# OUTPUTS.net
KiCad netlist of a schematic drawn in Altium Designer
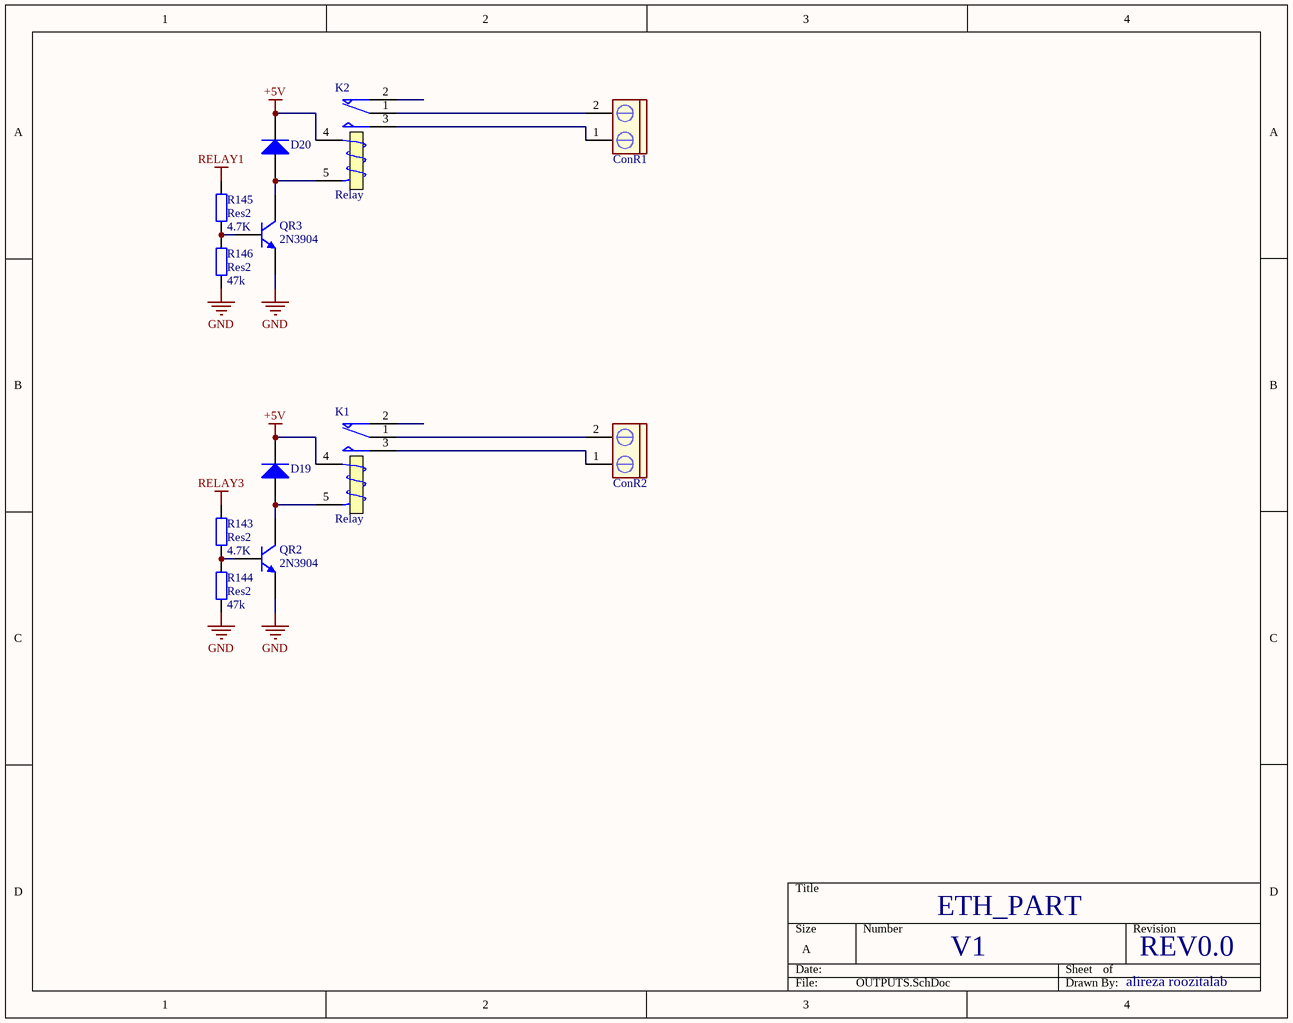
[diagram p0: OUTPUTS.SchDoc]

(export (version "E")
  (design (tool "Eeschema 10.0.6"))
  (components
    (comp (ref "ConR1")
      (value "CON2 pin blue")
      (footprint "My_CN2")
      (description "Connector blue screw")
      (libsource (lib "Mylib") (part "CON2 pin blue"))
    )
    (comp (ref "ConR2")
      (value "CON2 pin blue")
      (footprint "My_CN2")
      (description "Connector blue screw")
      (libsource (lib "Mylib") (part "CON2 pin blue"))
    )
    (comp (ref "D19")
      (value "Diode 1N4148")
      (footprint "Diode-1n4148 - SMD PAD")
      (description "High Conductance Fast Diode")
      (fields (field (name "PUBLISHER") "Altium Limited"))
      (libsource (lib "Miscellaneous Devices") (part "Diode 1N4148"))
    )
    (comp (ref "D20")
      (value "Diode 1N4148")
      (footprint "Diode-1n4148 - SMD PAD")
      (description "High Conductance Fast Diode")
      (fields (field (name "PUBLISHER") "Altium Limited"))
      (libsource (lib "Miscellaneous Devices") (part "Diode 1N4148"))
    )
    (comp (ref "K1")
      (value "Relay")
      (footprint "Relay 18.85x15.35x15.70")
      (description "SPDT Relay")
      (fields (field (name "PUBLISHER") "Altium Limited"))
      (libsource (lib "Miscellaneous Devices") (part "Relay"))
    )
    (comp (ref "K2")
      (value "Relay")
      (footprint "Relay 18.85x15.35x15.70")
      (description "SPDT Relay")
      (fields (field (name "PUBLISHER") "Altium Limited"))
      (libsource (lib "Miscellaneous Devices") (part "Relay"))
    )
    (comp (ref "QR2")
      (value "2N3904")
      (footprint "2N3906_SMD")
      (description "NPN General Purpose Amplifier")
      (fields (field (name "PUBLISHER") "Altium Limited"))
      (libsource (lib "Miscellaneous Devices") (part "2N3904"))
    )
    (comp (ref "QR3")
      (value "2N3904")
      (footprint "2N3906_SMD")
      (description "NPN General Purpose Amplifier")
      (fields (field (name "PUBLISHER") "Altium Limited"))
      (libsource (lib "Miscellaneous Devices") (part "2N3904"))
    )
    (comp (ref "R143")
      (value "Res2")
      (footprint "RES 1206 (3216X08L)")
      (description "Resistor")
      (fields (field (name "ALTIUM_VALUE") "4.7K") (field (name "PUBLISHER") "Altium Limited"))
      (libsource (lib "Miscellaneous Devices") (part "Res2"))
    )
    (comp (ref "R144")
      (value "Res2")
      (footprint "RES 1206 (3216X08L)")
      (description "Resistor")
      (fields (field (name "ALTIUM_VALUE") "47k") (field (name "PUBLISHER") "Altium Limited"))
      (libsource (lib "Miscellaneous Devices") (part "Res2"))
    )
    (comp (ref "R145")
      (value "Res2")
      (footprint "RES 1206 (3216X08L)")
      (description "Resistor")
      (fields (field (name "ALTIUM_VALUE") "4.7K") (field (name "PUBLISHER") "Altium Limited"))
      (libsource (lib "Miscellaneous Devices") (part "Res2"))
    )
    (comp (ref "R146")
      (value "Res2")
      (footprint "RES 1206 (3216X08L)")
      (description "Resistor")
      (fields (field (name "ALTIUM_VALUE") "47k") (field (name "PUBLISHER") "Altium Limited"))
      (libsource (lib "Miscellaneous Devices") (part "Res2"))
    )
  )
  (nets
    (net (code "1") (name "+5V") (class "Default")
      (node (ref "D19") (pin "2") (pinfunction "K_2") (pintype "passive"))
      (node (ref "D20") (pin "2") (pinfunction "K_2") (pintype "passive"))
      (node (ref "K1") (pin "4") (pinfunction "T1_4") (pintype "passive"))
      (node (ref "K2") (pin "4") (pinfunction "T1_4") (pintype "passive"))
    )
    (net (code "2") (name "GND") (class "Default")
      (node (ref "QR2") (pin "1") (pinfunction "E_1") (pintype "passive"))
      (node (ref "QR3") (pin "1") (pinfunction "E_1") (pintype "passive"))
      (node (ref "R144") (pin "1") (pinfunction "1_1") (pintype "passive"))
      (node (ref "R146") (pin "1") (pinfunction "1_1") (pintype "passive"))
    )
    (net (code "3") (name "Net-(D19-A)") (class "Default")
      (node (ref "D19") (pin "1") (pinfunction "A_1") (pintype "passive"))
      (node (ref "K1") (pin "5") (pinfunction "T2_5") (pintype "passive"))
      (node (ref "QR2") (pin "3") (pinfunction "C_3") (pintype "passive"))
    )
    (net (code "4") (name "Net-(D20-A)") (class "Default")
      (node (ref "D20") (pin "1") (pinfunction "A_1") (pintype "passive"))
      (node (ref "K2") (pin "5") (pinfunction "T2_5") (pintype "passive"))
      (node (ref "QR3") (pin "3") (pinfunction "C_3") (pintype "passive"))
    )
    (net (code "5") (name "Net-(K1-COM)") (class "Default")
      (node (ref "ConR2") (pin "2") (pinfunction "2_2") (pintype "passive"))
      (node (ref "K1") (pin "1") (pinfunction "COM_1") (pintype "passive"))
    )
    (net (code "6") (name "Net-(K1-NO)") (class "Default")
      (node (ref "ConR2") (pin "1") (pinfunction "1_1") (pintype "passive"))
      (node (ref "K1") (pin "3") (pinfunction "NO_3") (pintype "passive"))
    )
    (net (code "7") (name "Net-(K2-COM)") (class "Default")
      (node (ref "ConR1") (pin "2") (pinfunction "2_2") (pintype "passive"))
      (node (ref "K2") (pin "1") (pinfunction "COM_1") (pintype "passive"))
    )
    (net (code "8") (name "Net-(K2-NO)") (class "Default")
      (node (ref "ConR1") (pin "1") (pinfunction "1_1") (pintype "passive"))
      (node (ref "K2") (pin "3") (pinfunction "NO_3") (pintype "passive"))
    )
    (net (code "9") (name "Net-(QR2-B)") (class "Default")
      (node (ref "QR2") (pin "2") (pinfunction "B_2") (pintype "passive"))
      (node (ref "R143") (pin "1") (pinfunction "1_1") (pintype "passive"))
      (node (ref "R144") (pin "2") (pinfunction "2_2") (pintype "passive"))
    )
    (net (code "10") (name "Net-(QR3-B)") (class "Default")
      (node (ref "QR3") (pin "2") (pinfunction "B_2") (pintype "passive"))
      (node (ref "R145") (pin "1") (pinfunction "1_1") (pintype "passive"))
      (node (ref "R146") (pin "2") (pinfunction "2_2") (pintype "passive"))
    )
    (net (code "11") (name "RELAY1") (class "Default")
      (node (ref "R145") (pin "2") (pinfunction "2_2") (pintype "passive"))
    )
    (net (code "12") (name "RELAY3") (class "Default")
      (node (ref "R143") (pin "2") (pinfunction "2_2") (pintype "passive"))
    )
    (net (code "13") (name "unconnected-(K1-NC-Pad2)") (class "Default")
      (node (ref "K1") (pin "2") (pinfunction "NC_2") (pintype "passive"))
    )
    (net (code "14") (name "unconnected-(K2-NC-Pad2)") (class "Default")
      (node (ref "K2") (pin "2") (pinfunction "NC_2") (pintype "passive"))
    )
  )
)
